# DAU_Kupplung_1_phasig_V1_10.net
KiCad netlist of a schematic drawn in EAGLE
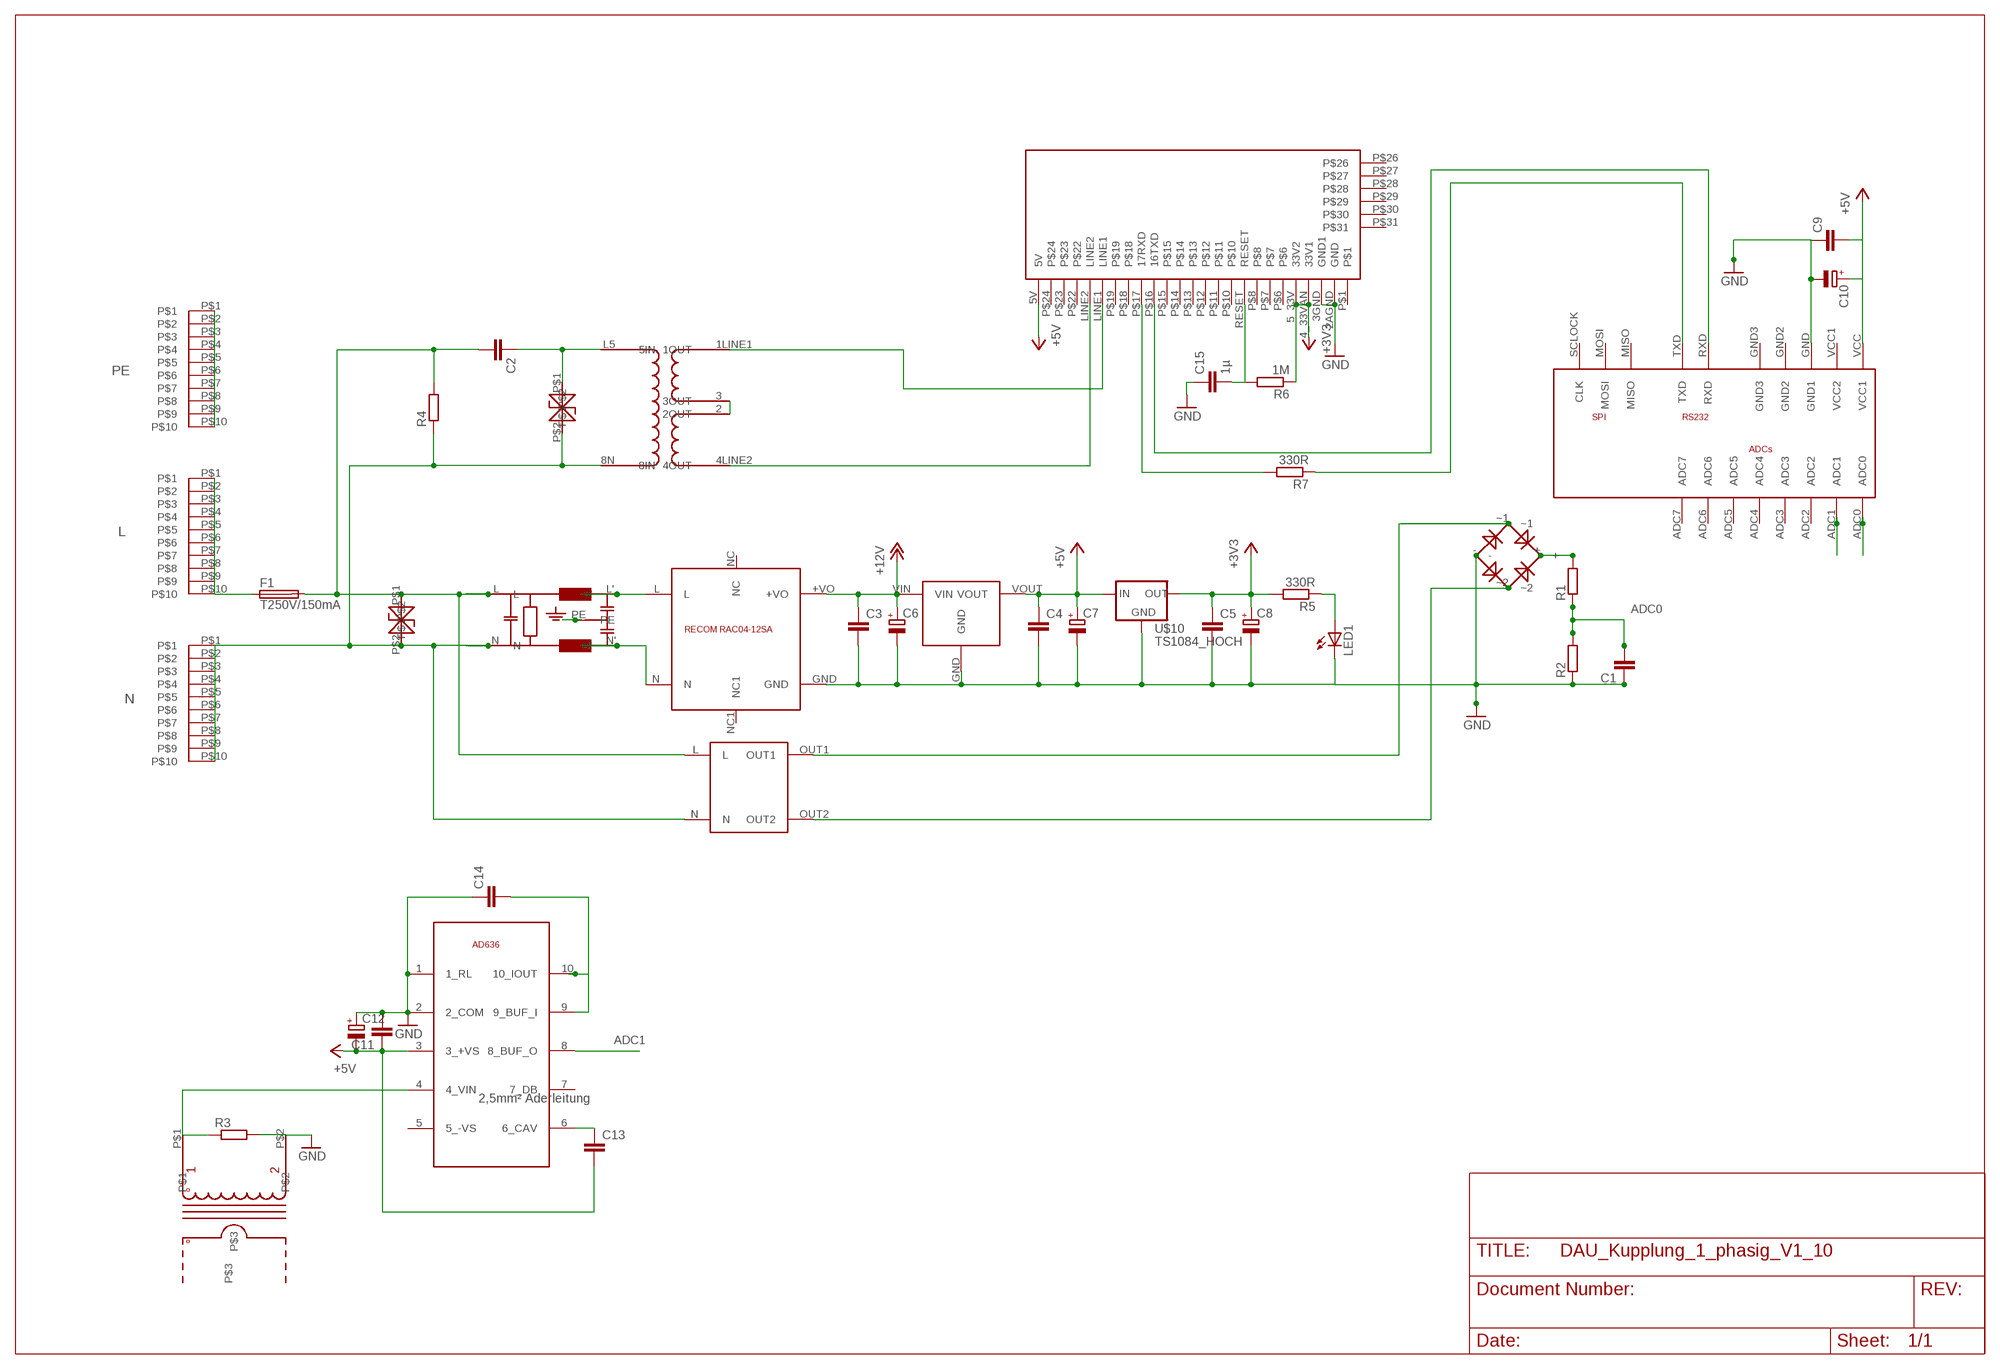
[diagram p0: schematic, sheet 1]

(export (version "E")
  (design (tool "Eeschema 10.0.6"))
  (components
    (comp (ref "C1")
      (value "C2,5-3")
      (footprint "eagle-import:C2.5-3")
      (libsource (lib "eagle-import") (part "C2,5-3"))
    )
    (comp (ref "C2")
      (value "C-EU225-087X268")
      (footprint "eagle-import:C225-087X268")
      (libsource (lib "eagle-import") (part "resistor_C-EU225-087X268"))
    )
    (comp (ref "C3")
      (value "C-EUC0805")
      (footprint "eagle-import:C0805")
      (libsource (lib "eagle-import") (part "resistor_C-EUC0805"))
    )
    (comp (ref "C4")
      (value "C-EUC0805")
      (footprint "eagle-import:C0805")
      (libsource (lib "eagle-import") (part "resistor_C-EUC0805"))
    )
    (comp (ref "C5")
      (value "C-EUC0805")
      (footprint "eagle-import:C0805")
      (libsource (lib "eagle-import") (part "resistor_C-EUC0805"))
    )
    (comp (ref "C6")
      (value "CPOL-EUE2.5-6")
      (footprint "eagle-import:E2,5-6")
      (libsource (lib "eagle-import") (part "resistor_CPOL-EUE2.5-6"))
    )
    (comp (ref "C7")
      (value "CPOL-EUE2.5-6")
      (footprint "eagle-import:E2,5-6")
      (libsource (lib "eagle-import") (part "resistor_CPOL-EUE2.5-6"))
    )
    (comp (ref "C8")
      (value "CPOL-EUE2.5-6")
      (footprint "eagle-import:E2,5-6")
      (libsource (lib "eagle-import") (part "resistor_CPOL-EUE2.5-6"))
    )
    (comp (ref "C9")
      (value "C-EUC0805")
      (footprint "eagle-import:C0805")
      (libsource (lib "eagle-import") (part "C-EUC0805"))
    )
    (comp (ref "C10")
      (value "CPOL-EUE2,5-6E")
      (footprint "eagle-import:E2,5-6E")
      (libsource (lib "eagle-import") (part "CPOL-EUE2,5-6E"))
    )
    (comp (ref "C11")
      (value "C-EUC0805")
      (footprint "eagle-import:C0805")
      (libsource (lib "eagle-import") (part "C-EUC0805"))
    )
    (comp (ref "C12")
      (value "CPOL-EUE2,5-6E")
      (footprint "eagle-import:E2,5-6E")
      (libsource (lib "eagle-import") (part "CPOL-EUE2,5-6E"))
    )
    (comp (ref "C13")
      (value "C-EUC0805")
      (footprint "eagle-import:C0805")
      (libsource (lib "eagle-import") (part "C-EUC0805"))
    )
    (comp (ref "C14")
      (value "C-EUC0805")
      (footprint "eagle-import:C0805")
      (libsource (lib "eagle-import") (part "C-EUC0805"))
    )
    (comp (ref "C15")
      (value "1µ")
      (footprint "eagle-import:C0805")
      (libsource (lib "eagle-import") (part "resistor_C-EUC0805"))
    )
    (comp (ref "F1")
      (value "T250V/150mA")
      (footprint "eagle-import:TR5")
      (libsource (lib "eagle-import") (part "TR5"))
    )
    (comp (ref "L")
      (value "PRINT_CONNECTOR")
      (footprint "eagle-import:FASTON_DOUBLE")
      (libsource (lib "eagle-import") (part "PRINT_CONNECTOR"))
    )
    (comp (ref "LED1")
      (value "LEDSQR2X5")
      (footprint "eagle-import:LED2X5")
      (libsource (lib "eagle-import") (part "LEDSQR2X5"))
    )
    (comp (ref "N")
      (value "PRINT_CONNECTOR")
      (footprint "eagle-import:FASTON_DOUBLE")
      (libsource (lib "eagle-import") (part "PRINT_CONNECTOR"))
    )
    (comp (ref "PE")
      (value "PRINT_CONNECTOR")
      (footprint "eagle-import:FASTON_DOUBLE")
      (libsource (lib "eagle-import") (part "PRINT_CONNECTOR"))
    )
    (comp (ref "R1")
      (value "R-EU_0204/7")
      (footprint "eagle-import:0204_7")
      (libsource (lib "eagle-import") (part "R-EU_0204/7"))
    )
    (comp (ref "R2")
      (value "R-EU_0204/7")
      (footprint "eagle-import:0204_7")
      (libsource (lib "eagle-import") (part "R-EU_0204/7"))
    )
    (comp (ref "R3")
      (value "R-EU_0204/7")
      (footprint "eagle-import:0204_7")
      (libsource (lib "eagle-import") (part "R-EU_0204/7"))
    )
    (comp (ref "R4")
      (value "R-EU_0204/7")
      (footprint "eagle-import:0204_7")
      (libsource (lib "eagle-import") (part "R-EU_0204/7"))
    )
    (comp (ref "R5")
      (value "330R")
      (footprint "eagle-import:0204_7")
      (libsource (lib "eagle-import") (part "R-EU_0204/7"))
    )
    (comp (ref "R6")
      (value "1M")
      (footprint "eagle-import:0204_7")
      (libsource (lib "eagle-import") (part "R-EU_0204/7"))
    )
    (comp (ref "R7")
      (value "330R")
      (footprint "eagle-import:0204_7")
      (libsource (lib "eagle-import") (part "R-EU_0204/7"))
    )
    (comp (ref "U$1")
      (value "RECOM_RAC04_12SA")
      (footprint "eagle-import:RAC04_12SA")
      (libsource (lib "eagle-import") (part "RECOM_RAC04_12SA"))
    )
    (comp (ref "U$2")
      (value "SICHERHEITSTRAFO")
      (footprint "eagle-import:TRAFO_0,35VA")
      (libsource (lib "eagle-import") (part "SICHERHEITSTRAFO"))
    )
    (comp (ref "U$3")
      (value "ADUC831_MINIMUM")
      (footprint "eagle-import:ADUC_MINIMUM")
      (libsource (lib "eagle-import") (part "ADUC831_MINIMUM"))
    )
    (comp (ref "U$4")
      (value "IT800")
      (footprint "eagle-import:IT800")
      (libsource (lib "eagle-import") (part "IT800"))
    )
    (comp (ref "U$5")
      (value "PLC_UEBERTRAGER_V2")
      (footprint "eagle-import:PLC-UEBERTRAGER_V2")
      (libsource (lib "eagle-import") (part "PLC_UEBERTRAGER_V2"))
    )
    (comp (ref "U$6")
      (value "AC1010")
      (footprint "eagle-import:AC1010")
      (libsource (lib "eagle-import") (part "AC1010"))
    )
    (comp (ref "U$7")
      (value "AD636")
      (footprint "eagle-import:TO100_10PIN")
      (libsource (lib "eagle-import") (part "AD636"))
    )
    (comp (ref "U$8")
      (value "RECTIFIER")
      (footprint "eagle-import:RECTIFIER")
      (libsource (lib "eagle-import") (part "RECTIFIER"))
    )
    (comp (ref "U$9")
      (value "TSV")
      (footprint "eagle-import:TSV")
      (libsource (lib "eagle-import") (part "TSV"))
    )
    (comp (ref "U$10")
      (value "TS1084_HOCH")
      (footprint "eagle-import:TS1084_HOCH")
      (libsource (lib "eagle-import") (part "TS1084_HOCH"))
    )
    (comp (ref "U$11")
      (value "RECOM_785_05")
      (footprint "eagle-import:RECOM785X")
      (libsource (lib "eagle-import") (part "RECOM_785_05"))
    )
    (comp (ref "U$12")
      (value "TSV")
      (footprint "eagle-import:TSV")
      (libsource (lib "eagle-import") (part "TSV"))
    )
    (comp (ref "U$13")
      (value "NETZFILTER_05_A")
      (footprint "eagle-import:NETZFILTER")
      (libsource (lib "eagle-import") (part "NETZFILTER_05_A"))
    )
  )
  (nets
    (net (code "1") (name "+3V3") (class "Default")
      (node (ref "C5") (pin "1") (pinfunction "1_1") (pintype "passive"))
      (node (ref "C8") (pin "+") (pinfunction "+_+") (pintype "passive"))
      (node (ref "R5") (pin "2") (pinfunction "2_2") (pintype "passive"))
      (node (ref "R6") (pin "1") (pinfunction "1_1") (pintype "passive"))
      (node (ref "U$10") (pin "OUT") (pinfunction "OUT_OUT") (pintype "passive"))
      (node (ref "U$4") (pin "4_33VAN") (pinfunction "33V1_4_33VAN") (pintype "bidirectional"))
      (node (ref "U$4") (pin "5_33V") (pinfunction "33V2_5_33V") (pintype "bidirectional"))
    )
    (net (code "2") (name "+5V") (class "Default")
      (node (ref "C10") (pin "+") (pinfunction "+_+") (pintype "passive"))
      (node (ref "C11") (pin "1") (pinfunction "1_1") (pintype "passive"))
      (node (ref "C12") (pin "-") (pinfunction "-_-") (pintype "passive"))
      (node (ref "C13") (pin "2") (pinfunction "2_2") (pintype "passive"))
      (node (ref "C4") (pin "1") (pinfunction "1_1") (pintype "passive"))
      (node (ref "C7") (pin "+") (pinfunction "+_+") (pintype "passive"))
      (node (ref "C9") (pin "2") (pinfunction "2_2") (pintype "passive"))
      (node (ref "U$10") (pin "IN") (pinfunction "IN_IN") (pintype "input"))
      (node (ref "U$11") (pin "VOUT") (pinfunction "VOUT_VOUT") (pintype "bidirectional"))
      (node (ref "U$3") (pin "VCC") (pinfunction "VCC1_VCC") (pintype "bidirectional"))
      (node (ref "U$4") (pin "5V") (pinfunction "5V_5V") (pintype "bidirectional"))
      (node (ref "U$7") (pin "3") (pinfunction "3_+VS_3") (pintype "input"))
    )
    (net (code "3") (name "+12V") (class "Default")
      (node (ref "C3") (pin "1") (pinfunction "1_1") (pintype "passive"))
      (node (ref "C6") (pin "+") (pinfunction "+_+") (pintype "passive"))
      (node (ref "U$1") (pin "+VO") (pinfunction "+VO_+VO") (pintype "bidirectional"))
      (node (ref "U$11") (pin "VIN") (pinfunction "VIN_VIN") (pintype "bidirectional"))
    )
    (net (code "4") (name "/ADC0") (class "Default")
      (node (ref "C1") (pin "2") (pinfunction "2_2") (pintype "passive"))
      (node (ref "R1") (pin "1") (pinfunction "1_1") (pintype "passive"))
      (node (ref "R2") (pin "2") (pinfunction "2_2") (pintype "passive"))
      (node (ref "U$3") (pin "ADC0") (pinfunction "ADC0_ADC0") (pintype "bidirectional"))
    )
    (net (code "5") (name "/ADC1") (class "Default")
      (node (ref "U$3") (pin "ADC1") (pinfunction "ADC1_ADC1") (pintype "bidirectional"))
      (node (ref "U$7") (pin "8") (pinfunction "8_BUF_O_8") (pintype "output"))
    )
    (net (code "6") (name "/PE") (class "Default")
      (node (ref "PE") (pin "P$1") (pinfunction "P$1_P$1") (pintype "bidirectional"))
      (node (ref "PE") (pin "P$10") (pinfunction "P$10_P$10") (pintype "bidirectional"))
      (node (ref "PE") (pin "P$2") (pinfunction "P$2_P$2") (pintype "bidirectional"))
      (node (ref "PE") (pin "P$3") (pinfunction "P$3_P$3") (pintype "bidirectional"))
      (node (ref "PE") (pin "P$4") (pinfunction "P$4_P$4") (pintype "bidirectional"))
      (node (ref "PE") (pin "P$5") (pinfunction "P$5_P$5") (pintype "bidirectional"))
      (node (ref "PE") (pin "P$6") (pinfunction "P$6_P$6") (pintype "bidirectional"))
      (node (ref "PE") (pin "P$7") (pinfunction "P$7_P$7") (pintype "bidirectional"))
      (node (ref "PE") (pin "P$8") (pinfunction "P$8_P$8") (pintype "bidirectional"))
      (node (ref "PE") (pin "P$9") (pinfunction "P$9_P$9") (pintype "bidirectional"))
      (node (ref "U$13") (pin "PE") (pinfunction "PE_PE") (pintype "input"))
    )
    (net (code "7") (name "GND") (class "Default")
      (node (ref "C1") (pin "1") (pinfunction "1_1") (pintype "passive"))
      (node (ref "C10") (pin "-") (pinfunction "-_-") (pintype "passive"))
      (node (ref "C11") (pin "2") (pinfunction "2_2") (pintype "passive"))
      (node (ref "C12") (pin "+") (pinfunction "+_+") (pintype "passive"))
      (node (ref "C14") (pin "1") (pinfunction "1_1") (pintype "passive"))
      (node (ref "C15") (pin "1") (pinfunction "1_1") (pintype "passive"))
      (node (ref "C3") (pin "2") (pinfunction "2_2") (pintype "passive"))
      (node (ref "C4") (pin "2") (pinfunction "2_2") (pintype "passive"))
      (node (ref "C5") (pin "2") (pinfunction "2_2") (pintype "passive"))
      (node (ref "C6") (pin "-") (pinfunction "-_-") (pintype "passive"))
      (node (ref "C7") (pin "-") (pinfunction "-_-") (pintype "passive"))
      (node (ref "C8") (pin "-") (pinfunction "-_-") (pintype "passive"))
      (node (ref "C9") (pin "1") (pinfunction "1_1") (pintype "passive"))
      (node (ref "LED1") (pin "K") (pinfunction "C_K") (pintype "passive"))
      (node (ref "R2") (pin "1") (pinfunction "1_1") (pintype "passive"))
      (node (ref "R3") (pin "2") (pinfunction "2_2") (pintype "passive"))
      (node (ref "U$1") (pin "GND") (pinfunction "GND_GND") (pintype "bidirectional"))
      (node (ref "U$10") (pin "GND") (pinfunction "GND_GND") (pintype "input"))
      (node (ref "U$11") (pin "GND") (pinfunction "GND_GND") (pintype "bidirectional"))
      (node (ref "U$3") (pin "GND") (pinfunction "GND1_GND") (pintype "bidirectional"))
      (node (ref "U$4") (pin "2AGND") (pinfunction "GND_2AGND") (pintype "bidirectional"))
      (node (ref "U$4") (pin "3GND") (pinfunction "GND1_3GND") (pintype "bidirectional"))
      (node (ref "U$6") (pin "P$2") (pinfunction "P$2_P$2") (pintype "bidirectional"))
      (node (ref "U$7") (pin "1") (pinfunction "1_RL_1") (pintype "bidirectional"))
      (node (ref "U$7") (pin "2") (pinfunction "2_COM_2") (pintype "bidirectional"))
      (node (ref "U$8") (pin "-") (pinfunction "-_-") (pintype "bidirectional"))
    )
    (net (code "8") (name "Net-(C2-Pad2)") (class "Default")
      (node (ref "C2") (pin "2") (pinfunction "2_2") (pintype "passive"))
      (node (ref "F1") (pin "2") (pinfunction "2_2") (pintype "passive"))
      (node (ref "R4") (pin "2") (pinfunction "2_2") (pintype "passive"))
      (node (ref "U$13") (pin "L") (pinfunction "L_L") (pintype "bidirectional"))
      (node (ref "U$2") (pin "L") (pinfunction "L_L") (pintype "bidirectional"))
      (node (ref "U$9") (pin "P$1") (pinfunction "P$1_P$1") (pintype "bidirectional"))
    )
    (net (code "9") (name "Net-(C15-Pad2)") (class "Default")
      (node (ref "C15") (pin "2") (pinfunction "2_2") (pintype "passive"))
      (node (ref "R6") (pin "2") (pinfunction "2_2") (pintype "passive"))
      (node (ref "U$4") (pin "RESET") (pinfunction "RESET_RESET") (pintype "bidirectional"))
    )
    (net (code "10") (name "Net-(F1-Pad1)") (class "Default")
      (node (ref "F1") (pin "1") (pinfunction "1_1") (pintype "passive"))
      (node (ref "L") (pin "P$1") (pinfunction "P$1_P$1") (pintype "bidirectional"))
      (node (ref "L") (pin "P$10") (pinfunction "P$10_P$10") (pintype "bidirectional"))
      (node (ref "L") (pin "P$2") (pinfunction "P$2_P$2") (pintype "bidirectional"))
      (node (ref "L") (pin "P$3") (pinfunction "P$3_P$3") (pintype "bidirectional"))
      (node (ref "L") (pin "P$4") (pinfunction "P$4_P$4") (pintype "bidirectional"))
      (node (ref "L") (pin "P$5") (pinfunction "P$5_P$5") (pintype "bidirectional"))
      (node (ref "L") (pin "P$6") (pinfunction "P$6_P$6") (pintype "bidirectional"))
      (node (ref "L") (pin "P$7") (pinfunction "P$7_P$7") (pintype "bidirectional"))
      (node (ref "L") (pin "P$8") (pinfunction "P$8_P$8") (pintype "bidirectional"))
      (node (ref "L") (pin "P$9") (pinfunction "P$9_P$9") (pintype "bidirectional"))
    )
    (net (code "11") (name "Net-(LED1-PadA)") (class "Default")
      (node (ref "LED1") (pin "A") (pinfunction "A_A") (pintype "passive"))
      (node (ref "R5") (pin "1") (pinfunction "1_1") (pintype "passive"))
    )
    (net (code "12") (name "Net-(R1-Pad2)") (class "Default")
      (node (ref "R1") (pin "2") (pinfunction "2_2") (pintype "passive"))
      (node (ref "U$8") (pin "+") (pinfunction "+_+") (pintype "bidirectional"))
    )
    (net (code "13") (name "Net-(R7-Pad1)") (class "Default")
      (node (ref "R7") (pin "1") (pinfunction "1_1") (pintype "passive"))
      (node (ref "U$3") (pin "TXD") (pinfunction "TXD_TXD") (pintype "bidirectional"))
    )
    (net (code "14") (name "Net-(U$1-PadL)") (class "Default")
      (node (ref "U$1") (pin "L") (pinfunction "L_L") (pintype "bidirectional"))
      (node (ref "U$13") (pin "L'") (pinfunction "L'_L'") (pintype "bidirectional"))
    )
    (net (code "15") (name "Net-(U$1-PadN)") (class "Default")
      (node (ref "U$1") (pin "N") (pinfunction "N_N") (pintype "bidirectional"))
      (node (ref "U$13") (pin "N'") (pinfunction "N'_N'") (pintype "bidirectional"))
    )
    (net (code "16") (name "Net-(U$4-16TXD)") (class "Default")
      (node (ref "U$3") (pin "RXD") (pinfunction "RXD_RXD") (pintype "bidirectional"))
      (node (ref "U$4") (pin "P$16") (pinfunction "16TXD_P$16") (pintype "bidirectional"))
    )
    (net (code "17") (name "Net-(U$4-17RXD)") (class "Default")
      (node (ref "R7") (pin "2") (pinfunction "2_2") (pintype "passive"))
      (node (ref "U$4") (pin "P$17") (pinfunction "17RXD_P$17") (pintype "bidirectional"))
    )
    (net (code "18") (name "Net-(U$5-1OUT)") (class "Default")
      (node (ref "U$4") (pin "LINE1") (pinfunction "LINE1_LINE1") (pintype "bidirectional"))
      (node (ref "U$5") (pin "1LINE1") (pinfunction "1OUT_1LINE1") (pintype "output"))
    )
    (net (code "19") (name "Net-(U$5-2OUT)") (class "Default")
      (node (ref "U$5") (pin "2") (pinfunction "2OUT_2") (pintype "output"))
      (node (ref "U$5") (pin "3") (pinfunction "3OUT_3") (pintype "output"))
    )
    (net (code "20") (name "Net-(U$5-4OUT)") (class "Default")
      (node (ref "U$4") (pin "LINE2") (pinfunction "LINE2_LINE2") (pintype "bidirectional"))
      (node (ref "U$5") (pin "4LINE2") (pinfunction "4OUT_4LINE2") (pintype "output"))
    )
    (net (code "21") (name "Net-(U$5-5IN)") (class "Default")
      (node (ref "C2") (pin "1") (pinfunction "1_1") (pintype "passive"))
      (node (ref "U$12") (pin "P$1") (pinfunction "P$1_P$1") (pintype "bidirectional"))
      (node (ref "U$5") (pin "L5") (pinfunction "5IN_L5") (pintype "input"))
    )
    (net (code "22") (name "Net-(U$5-8IN)") (class "Default")
      (node (ref "N") (pin "P$1") (pinfunction "P$1_P$1") (pintype "bidirectional"))
      (node (ref "N") (pin "P$10") (pinfunction "P$10_P$10") (pintype "bidirectional"))
      (node (ref "N") (pin "P$2") (pinfunction "P$2_P$2") (pintype "bidirectional"))
      (node (ref "N") (pin "P$3") (pinfunction "P$3_P$3") (pintype "bidirectional"))
      (node (ref "N") (pin "P$4") (pinfunction "P$4_P$4") (pintype "bidirectional"))
      (node (ref "N") (pin "P$5") (pinfunction "P$5_P$5") (pintype "bidirectional"))
      (node (ref "N") (pin "P$6") (pinfunction "P$6_P$6") (pintype "bidirectional"))
      (node (ref "N") (pin "P$7") (pinfunction "P$7_P$7") (pintype "bidirectional"))
      (node (ref "N") (pin "P$8") (pinfunction "P$8_P$8") (pintype "bidirectional"))
      (node (ref "N") (pin "P$9") (pinfunction "P$9_P$9") (pintype "bidirectional"))
      (node (ref "R4") (pin "1") (pinfunction "1_1") (pintype "passive"))
      (node (ref "U$12") (pin "P$2") (pinfunction "P$2_P$2") (pintype "bidirectional"))
      (node (ref "U$13") (pin "N") (pinfunction "N_N") (pintype "bidirectional"))
      (node (ref "U$2") (pin "N") (pinfunction "N_N") (pintype "bidirectional"))
      (node (ref "U$5") (pin "8N") (pinfunction "8IN_8N") (pintype "input"))
      (node (ref "U$9") (pin "P$2") (pinfunction "P$2_P$2") (pintype "bidirectional"))
    )
    (net (code "23") (name "Net-(U$7-4_VIN)") (class "Default")
      (node (ref "R3") (pin "1") (pinfunction "1_1") (pintype "passive"))
      (node (ref "U$6") (pin "P$1") (pinfunction "P$1_P$1") (pintype "bidirectional"))
      (node (ref "U$7") (pin "4") (pinfunction "4_VIN_4") (pintype "input"))
    )
    (net (code "24") (name "Net-(U$7-6_CAV)") (class "Default")
      (node (ref "C13") (pin "1") (pinfunction "1_1") (pintype "passive"))
      (node (ref "U$7") (pin "6") (pinfunction "6_CAV_6") (pintype "input"))
    )
    (net (code "25") (name "Net-(U$7-10_IOUT)") (class "Default")
      (node (ref "C14") (pin "2") (pinfunction "2_2") (pintype "passive"))
      (node (ref "U$7") (pin "10") (pinfunction "10_IOUT_10") (pintype "output"))
      (node (ref "U$7") (pin "9") (pinfunction "9_BUF_I_9") (pintype "input"))
    )
    (net (code "26") (name "Net-(U$8-~{1})") (class "Default")
      (node (ref "U$2") (pin "OUT1") (pinfunction "OUT1_OUT1") (pintype "bidirectional"))
      (node (ref "U$8") (pin "~1") (pinfunction "~{1}_~1") (pintype "bidirectional"))
    )
    (net (code "27") (name "Net-(U$8-~{2})") (class "Default")
      (node (ref "U$2") (pin "OUT2") (pinfunction "OUT2_OUT2") (pintype "bidirectional"))
      (node (ref "U$8") (pin "~2") (pinfunction "~{2}_~2") (pintype "bidirectional"))
    )
    (net (code "28") (name "unconnected-(U$1-PadNC)") (class "Default")
      (node (ref "U$1") (pin "NC") (pinfunction "NC_NC") (pintype "bidirectional"))
    )
    (net (code "29") (name "unconnected-(U$1-PadNC1)") (class "Default")
      (node (ref "U$1") (pin "NC1") (pinfunction "NC1_NC1") (pintype "bidirectional"))
    )
    (net (code "30") (name "unconnected-(U$3-CLK-PadSCLOCK)") (class "Default")
      (node (ref "U$3") (pin "SCLOCK") (pinfunction "CLK_SCLOCK") (pintype "bidirectional"))
    )
    (net (code "31") (name "unconnected-(U$3-PadADC2)") (class "Default")
      (node (ref "U$3") (pin "ADC2") (pinfunction "ADC2_ADC2") (pintype "bidirectional"))
    )
    (net (code "32") (name "unconnected-(U$3-PadADC3)") (class "Default")
      (node (ref "U$3") (pin "ADC3") (pinfunction "ADC3_ADC3") (pintype "bidirectional"))
    )
    (net (code "33") (name "unconnected-(U$3-PadADC4)") (class "Default")
      (node (ref "U$3") (pin "ADC4") (pinfunction "ADC4_ADC4") (pintype "bidirectional"))
    )
    (net (code "34") (name "unconnected-(U$3-PadADC5)") (class "Default")
      (node (ref "U$3") (pin "ADC5") (pinfunction "ADC5_ADC5") (pintype "bidirectional"))
    )
    (net (code "35") (name "unconnected-(U$3-PadADC6)") (class "Default")
      (node (ref "U$3") (pin "ADC6") (pinfunction "ADC6_ADC6") (pintype "bidirectional"))
    )
    (net (code "36") (name "unconnected-(U$3-PadADC7)") (class "Default")
      (node (ref "U$3") (pin "ADC7") (pinfunction "ADC7_ADC7") (pintype "bidirectional"))
    )
    (net (code "37") (name "unconnected-(U$3-PadGND2)") (class "Default")
      (node (ref "U$3") (pin "GND2") (pinfunction "GND2_GND2") (pintype "bidirectional"))
    )
    (net (code "38") (name "unconnected-(U$3-PadGND3)") (class "Default")
      (node (ref "U$3") (pin "GND3") (pinfunction "GND3_GND3") (pintype "bidirectional"))
    )
    (net (code "39") (name "unconnected-(U$3-PadMISO)") (class "Default")
      (node (ref "U$3") (pin "MISO") (pinfunction "MISO_MISO") (pintype "bidirectional"))
    )
    (net (code "40") (name "unconnected-(U$3-PadMOSI)") (class "Default")
      (node (ref "U$3") (pin "MOSI") (pinfunction "MOSI_MOSI") (pintype "bidirectional"))
    )
    (net (code "41") (name "unconnected-(U$3-VCC2-PadVCC1)") (class "Default")
      (node (ref "U$3") (pin "VCC1") (pinfunction "VCC2_VCC1") (pintype "bidirectional"))
    )
    (net (code "42") (name "unconnected-(U$4-PadP$1)") (class "Default")
      (node (ref "U$4") (pin "P$1") (pinfunction "P$1_P$1") (pintype "bidirectional"))
    )
    (net (code "43") (name "unconnected-(U$4-PadP$6)") (class "Default")
      (node (ref "U$4") (pin "P$6") (pinfunction "P$6_P$6") (pintype "bidirectional"))
    )
    (net (code "44") (name "unconnected-(U$4-PadP$7)") (class "Default")
      (node (ref "U$4") (pin "P$7") (pinfunction "P$7_P$7") (pintype "bidirectional"))
    )
    (net (code "45") (name "unconnected-(U$4-PadP$8)") (class "Default")
      (node (ref "U$4") (pin "P$8") (pinfunction "P$8_P$8") (pintype "bidirectional"))
    )
    (net (code "46") (name "unconnected-(U$4-PadP$10)") (class "Default")
      (node (ref "U$4") (pin "P$10") (pinfunction "P$10_P$10") (pintype "bidirectional"))
    )
    (net (code "47") (name "unconnected-(U$4-PadP$11)") (class "Default")
      (node (ref "U$4") (pin "P$11") (pinfunction "P$11_P$11") (pintype "bidirectional"))
    )
    (net (code "48") (name "unconnected-(U$4-PadP$12)") (class "Default")
      (node (ref "U$4") (pin "P$12") (pinfunction "P$12_P$12") (pintype "bidirectional"))
    )
    (net (code "49") (name "unconnected-(U$4-PadP$13)") (class "Default")
      (node (ref "U$4") (pin "P$13") (pinfunction "P$13_P$13") (pintype "bidirectional"))
    )
    (net (code "50") (name "unconnected-(U$4-PadP$14)") (class "Default")
      (node (ref "U$4") (pin "P$14") (pinfunction "P$14_P$14") (pintype "bidirectional"))
    )
    (net (code "51") (name "unconnected-(U$4-PadP$15)") (class "Default")
      (node (ref "U$4") (pin "P$15") (pinfunction "P$15_P$15") (pintype "bidirectional"))
    )
    (net (code "52") (name "unconnected-(U$4-PadP$18)") (class "Default")
      (node (ref "U$4") (pin "P$18") (pinfunction "P$18_P$18") (pintype "bidirectional"))
    )
    (net (code "53") (name "unconnected-(U$4-PadP$19)") (class "Default")
      (node (ref "U$4") (pin "P$19") (pinfunction "P$19_P$19") (pintype "bidirectional"))
    )
    (net (code "54") (name "unconnected-(U$4-PadP$22)") (class "Default")
      (node (ref "U$4") (pin "P$22") (pinfunction "P$22_P$22") (pintype "bidirectional"))
    )
    (net (code "55") (name "unconnected-(U$4-PadP$23)") (class "Default")
      (node (ref "U$4") (pin "P$23") (pinfunction "P$23_P$23") (pintype "bidirectional"))
    )
    (net (code "56") (name "unconnected-(U$4-PadP$24)") (class "Default")
      (node (ref "U$4") (pin "P$24") (pinfunction "P$24_P$24") (pintype "bidirectional"))
    )
    (net (code "57") (name "unconnected-(U$4-PadP$26)") (class "Default")
      (node (ref "U$4") (pin "P$26") (pinfunction "P$26_P$26") (pintype "bidirectional"))
    )
    (net (code "58") (name "unconnected-(U$4-PadP$27)") (class "Default")
      (node (ref "U$4") (pin "P$27") (pinfunction "P$27_P$27") (pintype "bidirectional"))
    )
    (net (code "59") (name "unconnected-(U$4-PadP$28)") (class "Default")
      (node (ref "U$4") (pin "P$28") (pinfunction "P$28_P$28") (pintype "bidirectional"))
    )
    (net (code "60") (name "unconnected-(U$4-PadP$29)") (class "Default")
      (node (ref "U$4") (pin "P$29") (pinfunction "P$29_P$29") (pintype "bidirectional"))
    )
    (net (code "61") (name "unconnected-(U$4-PadP$30)") (class "Default")
      (node (ref "U$4") (pin "P$30") (pinfunction "P$30_P$30") (pintype "bidirectional"))
    )
    (net (code "62") (name "unconnected-(U$4-PadP$31)") (class "Default")
      (node (ref "U$4") (pin "P$31") (pinfunction "P$31_P$31") (pintype "bidirectional"))
    )
    (net (code "63") (name "unconnected-(U$6-PadP$3)") (class "Default")
      (node (ref "U$6") (pin "P$3") (pinfunction "P$3_P$3") (pintype "bidirectional"))
    )
    (net (code "64") (name "unconnected-(U$7-5_-VS-Pad5)") (class "Default")
      (node (ref "U$7") (pin "5") (pinfunction "5_-VS_5") (pintype "input"))
    )
    (net (code "65") (name "unconnected-(U$7-7_DB-Pad7)") (class "Default")
      (node (ref "U$7") (pin "7") (pinfunction "7_DB_7") (pintype "output"))
    )
  )
)
